# Sheet_all.net
KiCad netlist of a schematic drawn in Altium Designer
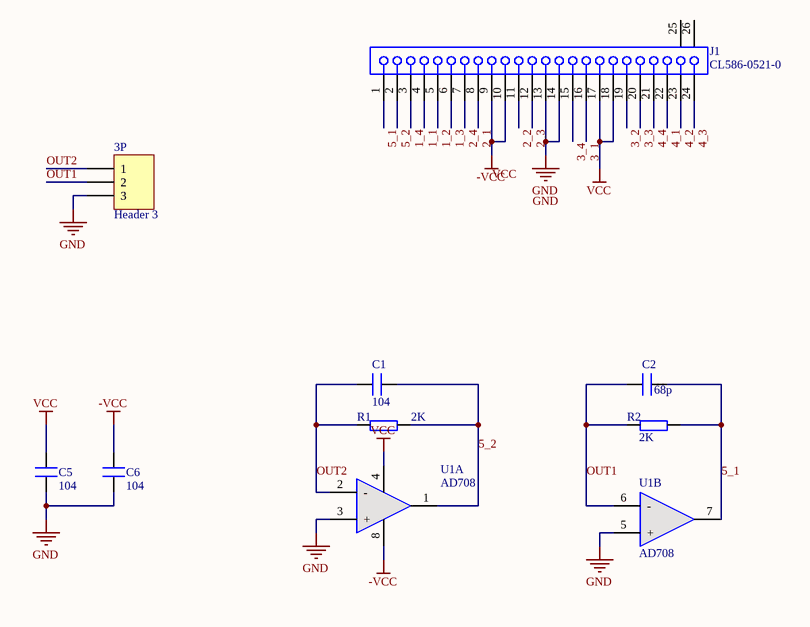
[diagram p0: Sheet_all.SchDoc]

(export (version "E")
  (design (tool "Eeschema 10.0.6"))
  (components
    (comp (ref "3P")
      (value "Header 3")
      (footprint "Header-1*3-2.54mm")
      (description "Header, 3-Pin")
      (fields (field (name "PUBLISHER") "Altium Limited"))
      (libsource (lib "接插件集成库") (part "Header 3"))
    )
    (comp (ref "C1") (value "104") (footprint "0603P") (libsource (lib "阿波罗STM32F4&F7底板封装库") (part "C")))
    (comp (ref "C2") (value "68p") (footprint "0603P") (libsource (lib "阿波罗STM32F4&F7底板封装库") (part "C")))
    (comp (ref "C5") (value "104") (footprint "0603P") (libsource (lib "阿波罗STM32F4&F7底板封装库") (part "C")))
    (comp (ref "C6") (value "104") (footprint "0603P") (libsource (lib "阿波罗STM32F4&F7底板封装库") (part "C")))
    (comp (ref "J1")
      (value "CL586-0521-0")
      (footprint "FH12-24S-0.5SH")
      (description "FH12 Series, \"Flip-Lock\" SMT/ZIF Connector - 0.5mm Spaced Bottom Contact")
      (fields (field (name "PUBLISHER") "Altium Limited"))
      (libsource (lib "HRS FPC-FFC FH12 Series") (part "CL586-0521-0"))
    )
    (comp (ref "R1") (value "2K") (footprint "0603P") (libsource (lib "阿波罗STM32F4&F7底板封装库") (part "R")))
    (comp (ref "R2") (value "2K") (footprint "0603P") (libsource (lib "阿波罗STM32F4&F7底板封装库") (part "R")))
    (comp (ref "U1")
      (value "AD708")
      (footprint "NSO8_N")
      (description "双运放")
      (libsource (lib "IC集成库") (part "LM358"))
    )
  )
  (nets
    (net (code "1") (name "-VCC") (class "Default")
      (node (ref "C6") (pin "2") (pintype "passive"))
      (node (ref "J1") (pin "10") (pinfunction "10_10") (pintype "passive"))
      (node (ref "J1") (pin "9") (pinfunction "9_9") (pintype "passive"))
      (node (ref "U1") (pin "8") (pinfunction "V+_8") (pintype "power_in"))
    )
    (net (code "2") (name "/1_1") (class "Default")
      (node (ref "J1") (pin "4") (pinfunction "4_4") (pintype "passive"))
    )
    (net (code "3") (name "/1_2") (class "Default")
      (node (ref "J1") (pin "5") (pinfunction "5_5") (pintype "passive"))
    )
    (net (code "4") (name "/1_3") (class "Default")
      (node (ref "J1") (pin "6") (pinfunction "6_6") (pintype "passive"))
    )
    (net (code "5") (name "/1_4") (class "Default")
      (node (ref "J1") (pin "3") (pinfunction "3_3") (pintype "passive"))
    )
    (net (code "6") (name "/2_1") (class "Default")
      (node (ref "J1") (pin "8") (pinfunction "8_8") (pintype "passive"))
    )
    (net (code "7") (name "/2_2") (class "Default")
      (node (ref "J1") (pin "11") (pinfunction "11_11") (pintype "passive"))
    )
    (net (code "8") (name "/2_3") (class "Default")
      (node (ref "J1") (pin "12") (pinfunction "12_12") (pintype "passive"))
    )
    (net (code "9") (name "/2_4") (class "Default")
      (node (ref "J1") (pin "7") (pinfunction "7_7") (pintype "passive"))
    )
    (net (code "10") (name "/3_1") (class "Default")
      (node (ref "J1") (pin "16") (pinfunction "16_16") (pintype "passive"))
    )
    (net (code "11") (name "/3_2") (class "Default")
      (node (ref "J1") (pin "19") (pinfunction "19_19") (pintype "passive"))
    )
    (net (code "12") (name "/3_3") (class "Default")
      (node (ref "J1") (pin "20") (pinfunction "20_20") (pintype "passive"))
    )
    (net (code "13") (name "/3_4") (class "Default")
      (node (ref "J1") (pin "15") (pinfunction "15_15") (pintype "passive"))
    )
    (net (code "14") (name "/4_1") (class "Default")
      (node (ref "J1") (pin "22") (pinfunction "22_22") (pintype "passive"))
    )
    (net (code "15") (name "/4_2") (class "Default")
      (node (ref "J1") (pin "23") (pinfunction "23_23") (pintype "passive"))
    )
    (net (code "16") (name "/4_3") (class "Default")
      (node (ref "J1") (pin "24") (pinfunction "24_24") (pintype "passive"))
    )
    (net (code "17") (name "/4_4") (class "Default")
      (node (ref "J1") (pin "21") (pinfunction "21_21") (pintype "passive"))
    )
    (net (code "18") (name "/5_1") (class "Default")
      (node (ref "C2") (pin "2") (pintype "passive"))
      (node (ref "J1") (pin "1") (pinfunction "1_1") (pintype "passive"))
      (node (ref "R2") (pin "2") (pintype "passive"))
      (node (ref "U1") (pin "7") (pinfunction "OUT2_7") (pintype "passive"))
    )
    (net (code "19") (name "/5_2") (class "Default")
      (node (ref "C1") (pin "2") (pintype "passive"))
      (node (ref "J1") (pin "2") (pinfunction "2_2") (pintype "passive"))
      (node (ref "R1") (pin "2") (pintype "passive"))
      (node (ref "U1") (pin "1") (pinfunction "OUT1_1") (pintype "passive"))
    )
    (net (code "20") (name "/OUT1") (class "Default")
      (node (ref "3P") (pin "2") (pinfunction "2_2") (pintype "passive"))
      (node (ref "C2") (pin "1") (pintype "passive"))
      (node (ref "R2") (pin "1") (pintype "passive"))
      (node (ref "U1") (pin "6") (pinfunction "-_6") (pintype "passive"))
    )
    (net (code "21") (name "/OUT2") (class "Default")
      (node (ref "3P") (pin "1") (pinfunction "1_1") (pintype "passive"))
      (node (ref "C1") (pin "1") (pintype "passive"))
      (node (ref "R1") (pin "1") (pintype "passive"))
      (node (ref "U1") (pin "2") (pinfunction "-_2") (pintype "passive"))
    )
    (net (code "22") (name "GND") (class "Default")
      (node (ref "3P") (pin "3") (pinfunction "3_3") (pintype "passive"))
      (node (ref "C5") (pin "1") (pintype "passive"))
      (node (ref "C6") (pin "1") (pintype "passive"))
      (node (ref "J1") (pin "13") (pinfunction "13_13") (pintype "passive"))
      (node (ref "J1") (pin "14") (pinfunction "14_14") (pintype "passive"))
      (node (ref "U1") (pin "3") (pinfunction "+_3") (pintype "passive"))
      (node (ref "U1") (pin "5") (pinfunction "+_5") (pintype "passive"))
    )
    (net (code "23") (name "VCC") (class "Default")
      (node (ref "C5") (pin "2") (pintype "passive"))
      (node (ref "J1") (pin "17") (pinfunction "17_17") (pintype "passive"))
      (node (ref "J1") (pin "18") (pinfunction "18_18") (pintype "passive"))
      (node (ref "U1") (pin "4") (pinfunction "V-_4") (pintype "power_in"))
    )
    (net (code "24") (name "unconnected-(J1-MH1-Pad25)") (class "Default")
      (node (ref "J1") (pin "25") (pinfunction "MH1_25") (pintype "passive"))
    )
    (net (code "25") (name "unconnected-(J1-MH2-Pad26)") (class "Default")
      (node (ref "J1") (pin "26") (pinfunction "MH2_26") (pintype "passive"))
    )
  )
)
